# Bottom-PCB.net
KiCad netlist of a schematic drawn in Altium Designer
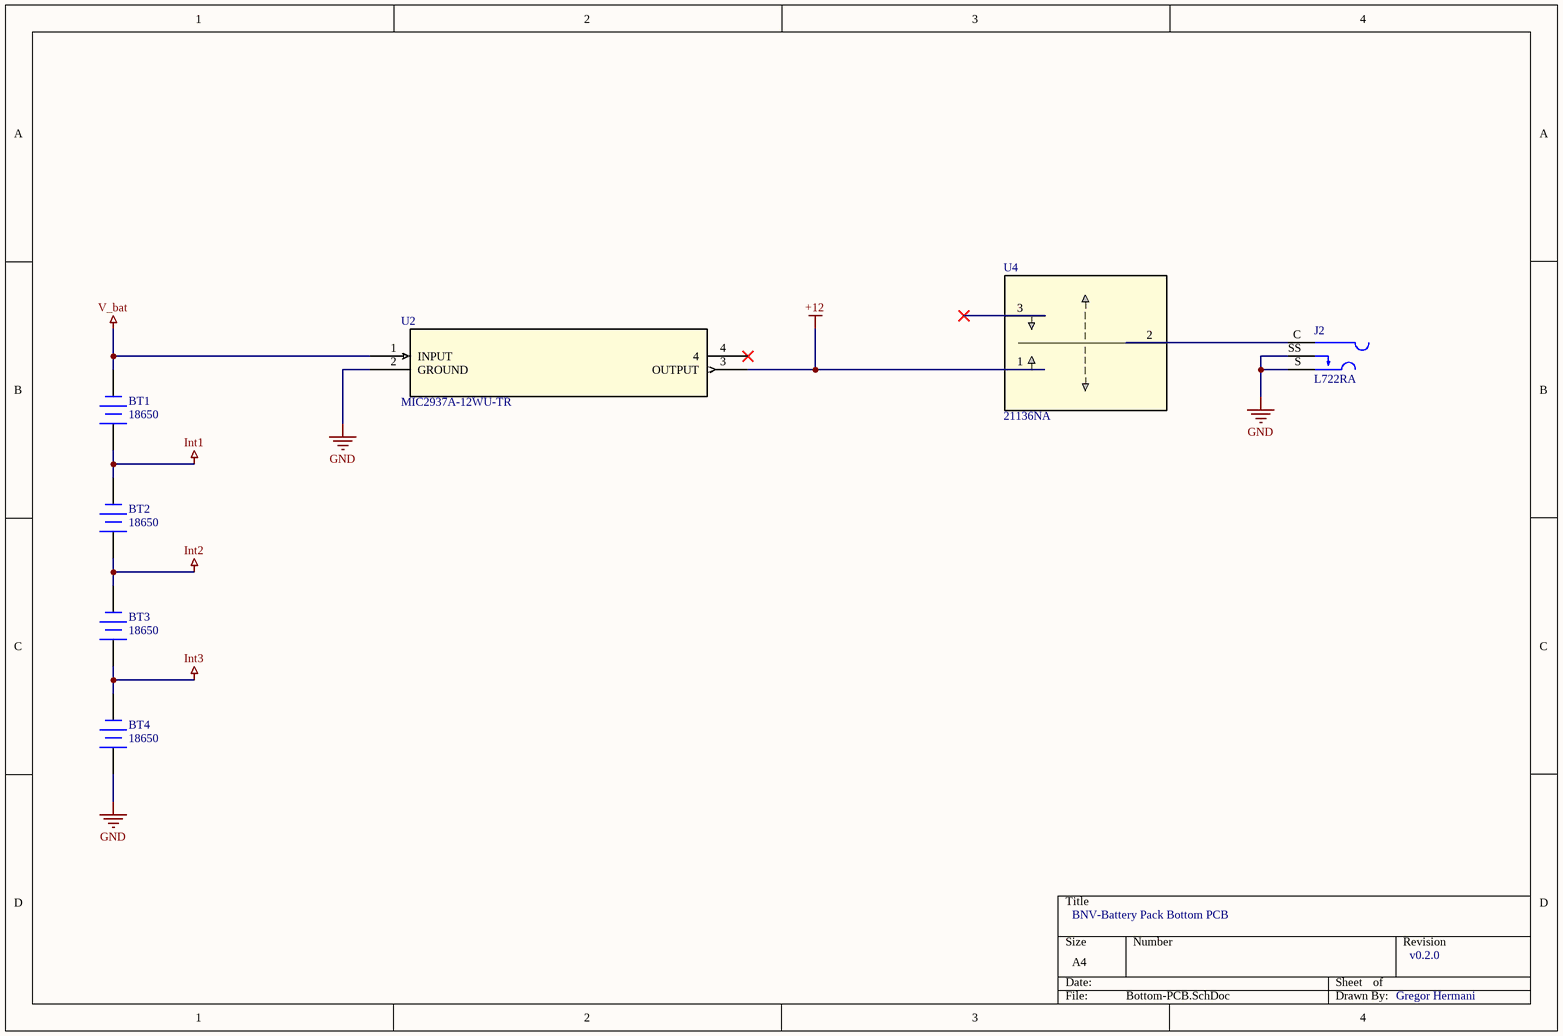
[diagram p0: Bottom-PCB.SchDoc]

(export (version "E")
  (design (tool "Eeschema 10.0.6"))
  (components
    (comp (ref "BT1")
      (value "18650")
      (footprint "BAT-2")
      (description "Multicell Battery")
      (fields (field (name "PUBLISHER") "Altium Limited"))
      (libsource (lib "Miscellaneous Devices") (part "Battery"))
    )
    (comp (ref "BT2")
      (value "18650")
      (footprint "BAT-2")
      (description "Multicell Battery")
      (fields (field (name "PUBLISHER") "Altium Limited"))
      (libsource (lib "Miscellaneous Devices") (part "Battery"))
    )
    (comp (ref "BT3")
      (value "18650")
      (footprint "BAT-2")
      (description "Multicell Battery")
      (fields (field (name "PUBLISHER") "Altium Limited"))
      (libsource (lib "Miscellaneous Devices") (part "Battery"))
    )
    (comp (ref "BT4")
      (value "18650")
      (footprint "BAT-2")
      (description "Multicell Battery")
      (fields (field (name "PUBLISHER") "Altium Limited"))
      (libsource (lib "Miscellaneous Devices") (part "Battery"))
    )
    (comp (ref "J2")
      (value "L722RA")
      (footprint "SWITCHCRAFT_L722RA")
      (libsource (lib "L722RA") (part "L722RA"))
    )
    (comp (ref "U2")
      (value "MIC2937A-12WU-TR")
      (footprint "TO-263-3_MCH")
      (description "No Description Available")
      (fields (field (name "COPYRIGHT") "Copyright (C) 2021 Ultra Librarian. All rights reserved."))
      (libsource (lib "MIC2937A-12WU-TR") (part "MIC2937A-12WU-TR"))
    )
    (comp (ref "U4")
      (value "21136NA")
      (footprint "SWITCH_21136_APM")
      (description "No Description Available")
      (fields (field (name "COPYRIGHT") "Copyright (C) 2021 Ultra Librarian. All rights reserved."))
      (libsource (lib "21136NA") (part "21136NA"))
    )
  )
  (nets
    (net (code "1") (name "+12") (class "Default")
      (node (ref "U2") (pin "3") (pinfunction "OUTPUT_3") (pintype "output"))
      (node (ref "U4") (pin "1") (pinfunction "1_1") (pintype "passive"))
    )
    (net (code "2") (name "GND") (class "Default")
      (node (ref "BT4") (pin "1") (pinfunction "+_1") (pintype "passive"))
      (node (ref "J2") (pin "S") (pinfunction "SLEEVE_S") (pintype "passive"))
      (node (ref "J2") (pin "SS") (pinfunction "SLEEVE_SHUNT_SS") (pintype "passive"))
      (node (ref "U2") (pin "2") (pinfunction "GROUND_2") (pintype "power_in"))
    )
    (net (code "3") (name "Int1") (class "Default")
      (node (ref "BT1") (pin "1") (pinfunction "+_1") (pintype "passive"))
      (node (ref "BT2") (pin "2") (pinfunction "-_2") (pintype "passive"))
    )
    (net (code "4") (name "Int2") (class "Default")
      (node (ref "BT2") (pin "1") (pinfunction "+_1") (pintype "passive"))
      (node (ref "BT3") (pin "2") (pinfunction "-_2") (pintype "passive"))
    )
    (net (code "5") (name "Int3") (class "Default")
      (node (ref "BT3") (pin "1") (pinfunction "+_1") (pintype "passive"))
      (node (ref "BT4") (pin "2") (pinfunction "-_2") (pintype "passive"))
    )
    (net (code "6") (name "Net-(J2-CENTRE_PIN)") (class "Default")
      (node (ref "J2") (pin "C") (pinfunction "CENTRE_PIN_C") (pintype "passive"))
      (node (ref "U4") (pin "2") (pinfunction "2_2") (pintype "passive"))
    )
    (net (code "7") (name "V_bat") (class "Default")
      (node (ref "BT1") (pin "2") (pinfunction "-_2") (pintype "passive"))
      (node (ref "U2") (pin "1") (pinfunction "INPUT_1") (pintype "input"))
    )
    (net (code "8") (name "unconnected-(U2-Pad4)") (class "Default")
      (node (ref "U2") (pin "4") (pinfunction "4_4") (pintype "passive+no_connect"))
    )
    (net (code "9") (name "unconnected-(U4-Pad3)") (class "Default")
      (node (ref "U4") (pin "3") (pinfunction "3_3") (pintype "passive+no_connect"))
    )
  )
)
